# sch_ma_eagle.net
KiCad netlist of a schematic drawn in EAGLE
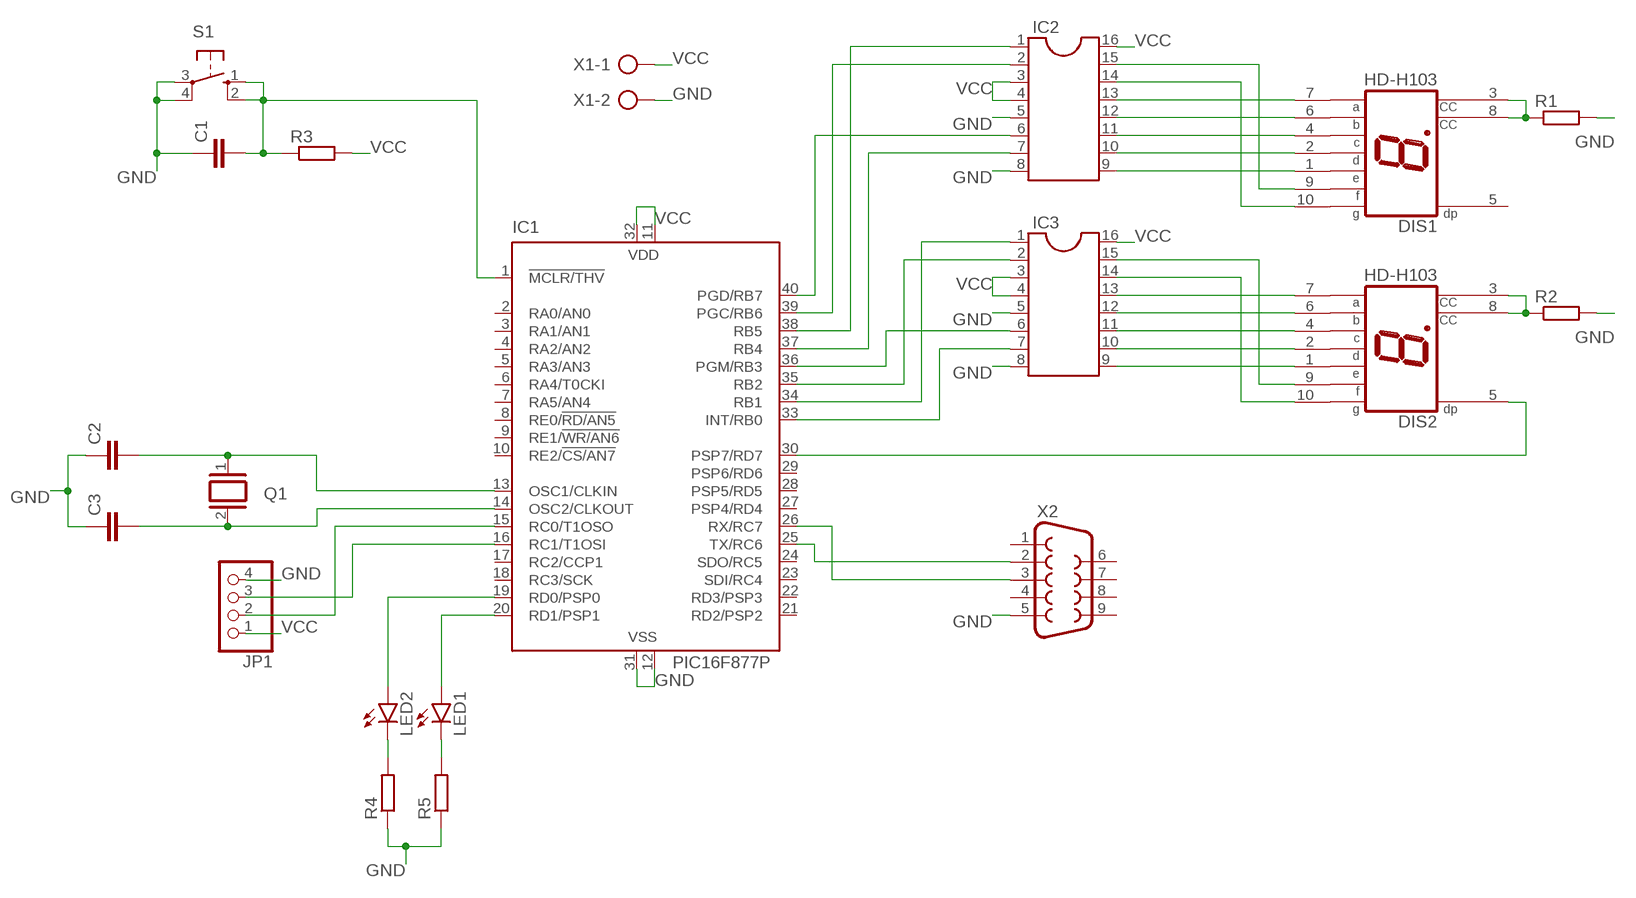
[diagram p0: schematic, sheet 1]

(export (version "E")
  (design (tool "Eeschema 10.0.6"))
  (components
    (comp (ref "C1")
      (value "C-EU025-025X050")
      (footprint "eagle-import:C025-025X050")
      (libsource (lib "eagle-import") (part "C-EU025-025X050"))
    )
    (comp (ref "C2")
      (value "C-EU025-025X050")
      (footprint "eagle-import:C025-025X050")
      (libsource (lib "eagle-import") (part "C-EU025-025X050"))
    )
    (comp (ref "C3")
      (value "C-EU025-025X050")
      (footprint "eagle-import:C025-025X050")
      (libsource (lib "eagle-import") (part "C-EU025-025X050"))
    )
    (comp (ref "DIS1")
      (value "HD-H103")
      (footprint "eagle-import:HDSP-M")
      (libsource (lib "eagle-import") (part "HD-H103"))
    )
    (comp (ref "DIS2")
      (value "HD-H103")
      (footprint "eagle-import:HDSP-M")
      (libsource (lib "eagle-import") (part "HD-H103"))
    )
    (comp (ref "IC1")
      (value "PIC16F877P")
      (footprint "eagle-import:DIL40")
      (fields (field (name "MF") "MICROCHIP") (field (name "MPN") "PIC16F877-04/P"))
      (libsource (lib "eagle-import") (part "PIC16F87P7"))
    )
    (comp (ref "IC2")
      (value "DIL16")
      (footprint "eagle-import:DIL16")
      (libsource (lib "eagle-import") (part "DIL16"))
    )
    (comp (ref "IC3")
      (value "DIL16")
      (footprint "eagle-import:DIL16")
      (libsource (lib "eagle-import") (part "DIL16"))
    )
    (comp (ref "JP1")
      (value "PINHD-1X4")
      (footprint "eagle-import:1X04")
      (libsource (lib "eagle-import") (part "PINHD-1X4"))
    )
    (comp (ref "LED1")
      (value "LED5MM")
      (footprint "eagle-import:LED5MM")
      (libsource (lib "eagle-import") (part "LED5MM"))
    )
    (comp (ref "LED2")
      (value "LED5MM")
      (footprint "eagle-import:LED5MM")
      (libsource (lib "eagle-import") (part "LED5MM"))
    )
    (comp (ref "Q1")
      (value "XTAL/S")
      (footprint "eagle-import:QS")
      (libsource (lib "eagle-import") (part "XTAL/S"))
    )
    (comp (ref "R1")
      (value "R-EU_0207/10")
      (footprint "eagle-import:0207_10")
      (libsource (lib "eagle-import") (part "R-EU_0207/10"))
    )
    (comp (ref "R2")
      (value "R-EU_0207/10")
      (footprint "eagle-import:0207_10")
      (libsource (lib "eagle-import") (part "R-EU_0207/10"))
    )
    (comp (ref "R3")
      (value "R-EU_0207/10")
      (footprint "eagle-import:0207_10")
      (libsource (lib "eagle-import") (part "R-EU_0207/10"))
    )
    (comp (ref "R4")
      (value "R-EU_0207/10")
      (footprint "eagle-import:0207_10")
      (libsource (lib "eagle-import") (part "R-EU_0207/10"))
    )
    (comp (ref "R5")
      (value "R-EU_0207/10")
      (footprint "eagle-import:0207_10")
      (libsource (lib "eagle-import") (part "R-EU_0207/10"))
    )
    (comp (ref "S1")
      (value "10-XX")
      (footprint "eagle-import:B3F-10XX")
      (fields (field (name "MPN") "B3F-1000"))
      (libsource (lib "eagle-import") (part "10-XX"))
    )
    (comp (ref "X1")
      (value "AK300/2")
      (footprint "eagle-import:AK300_2")
      (libsource (lib "eagle-import") (part "AK300/2"))
    )
    (comp (ref "X2")
      (value "F09H")
      (footprint "eagle-import:F09H")
      (libsource (lib "eagle-import") (part "F09H"))
    )
  )
  (nets
    (net (code "1") (name "/GND") (class "Default")
      (node (ref "C1") (pin "1") (pinfunction "1_1") (pintype "passive"))
      (node (ref "C2") (pin "1") (pinfunction "1_1") (pintype "passive"))
      (node (ref "C3") (pin "1") (pinfunction "1_1") (pintype "passive"))
      (node (ref "IC1") (pin "12") (pinfunction "VSS_12") (pintype "power_in"))
      (node (ref "IC1") (pin "31") (pinfunction "VSS_31") (pintype "power_in"))
      (node (ref "IC2") (pin "5") (pinfunction "5_5") (pintype "passive"))
      (node (ref "IC2") (pin "8") (pinfunction "8_8") (pintype "passive"))
      (node (ref "IC3") (pin "5") (pinfunction "5_5") (pintype "passive"))
      (node (ref "IC3") (pin "8") (pinfunction "8_8") (pintype "passive"))
      (node (ref "JP1") (pin "4") (pinfunction "4_4") (pintype "passive"))
      (node (ref "R1") (pin "2") (pinfunction "2_2") (pintype "passive"))
      (node (ref "R2") (pin "2") (pinfunction "2_2") (pintype "passive"))
      (node (ref "R4") (pin "1") (pinfunction "1_1") (pintype "passive"))
      (node (ref "R5") (pin "1") (pinfunction "1_1") (pintype "passive"))
      (node (ref "S1") (pin "3") (pinfunction "P_3") (pintype "passive"))
      (node (ref "S1") (pin "4") (pinfunction "P1_4") (pintype "passive"))
      (node (ref "X1") (pin "2") (pinfunction "KL_2") (pintype "passive"))
      (node (ref "X2") (pin "5") (pinfunction "5_5") (pintype "passive"))
    )
    (net (code "2") (name "/VCC") (class "Default")
      (node (ref "IC1") (pin "11") (pinfunction "VDD_11") (pintype "power_in"))
      (node (ref "IC1") (pin "32") (pinfunction "VDD_32") (pintype "power_in"))
      (node (ref "IC2") (pin "16") (pinfunction "16_16") (pintype "passive"))
      (node (ref "IC2") (pin "3") (pinfunction "3_3") (pintype "passive"))
      (node (ref "IC2") (pin "4") (pinfunction "4_4") (pintype "passive"))
      (node (ref "IC3") (pin "16") (pinfunction "16_16") (pintype "passive"))
      (node (ref "IC3") (pin "3") (pinfunction "3_3") (pintype "passive"))
      (node (ref "IC3") (pin "4") (pinfunction "4_4") (pintype "passive"))
      (node (ref "JP1") (pin "1") (pinfunction "1_1") (pintype "passive"))
      (node (ref "R3") (pin "2") (pinfunction "2_2") (pintype "passive"))
      (node (ref "X1") (pin "1") (pinfunction "KL_1") (pintype "passive"))
    )
    (net (code "3") (name "Net-(DIS1-A)") (class "Default")
      (node (ref "DIS1") (pin "7") (pinfunction "A_7") (pintype "passive"))
      (node (ref "IC2") (pin "13") (pinfunction "13_13") (pintype "passive"))
    )
    (net (code "4") (name "Net-(DIS1-B)") (class "Default")
      (node (ref "DIS1") (pin "6") (pinfunction "B_6") (pintype "passive"))
      (node (ref "IC2") (pin "12") (pinfunction "12_12") (pintype "passive"))
    )
    (net (code "5") (name "Net-(DIS1-C)") (class "Default")
      (node (ref "DIS1") (pin "4") (pinfunction "C_4") (pintype "passive"))
      (node (ref "IC2") (pin "11") (pinfunction "11_11") (pintype "passive"))
    )
    (net (code "6") (name "Net-(DIS1-CC-Pad3)") (class "Default")
      (node (ref "DIS1") (pin "3") (pinfunction "CC_3") (pintype "passive"))
      (node (ref "DIS1") (pin "8") (pinfunction "CC_8") (pintype "passive"))
      (node (ref "R1") (pin "1") (pinfunction "1_1") (pintype "passive"))
    )
    (net (code "7") (name "Net-(DIS1-D)") (class "Default")
      (node (ref "DIS1") (pin "2") (pinfunction "D_2") (pintype "passive"))
      (node (ref "IC2") (pin "10") (pinfunction "10_10") (pintype "passive"))
    )
    (net (code "8") (name "Net-(DIS1-E)") (class "Default")
      (node (ref "DIS1") (pin "1") (pinfunction "E_1") (pintype "passive"))
      (node (ref "IC2") (pin "9") (pinfunction "9_9") (pintype "passive"))
    )
    (net (code "9") (name "Net-(DIS1-F)") (class "Default")
      (node (ref "DIS1") (pin "9") (pinfunction "F_9") (pintype "passive"))
      (node (ref "IC2") (pin "15") (pinfunction "15_15") (pintype "passive"))
    )
    (net (code "10") (name "Net-(DIS1-G)") (class "Default")
      (node (ref "DIS1") (pin "10") (pinfunction "G_10") (pintype "passive"))
      (node (ref "IC2") (pin "14") (pinfunction "14_14") (pintype "passive"))
    )
    (net (code "11") (name "Net-(DIS2-A)") (class "Default")
      (node (ref "DIS2") (pin "7") (pinfunction "A_7") (pintype "passive"))
      (node (ref "IC3") (pin "13") (pinfunction "13_13") (pintype "passive"))
    )
    (net (code "12") (name "Net-(DIS2-B)") (class "Default")
      (node (ref "DIS2") (pin "6") (pinfunction "B_6") (pintype "passive"))
      (node (ref "IC3") (pin "12") (pinfunction "12_12") (pintype "passive"))
    )
    (net (code "13") (name "Net-(DIS2-C)") (class "Default")
      (node (ref "DIS2") (pin "4") (pinfunction "C_4") (pintype "passive"))
      (node (ref "IC3") (pin "11") (pinfunction "11_11") (pintype "passive"))
    )
    (net (code "14") (name "Net-(DIS2-CC-Pad3)") (class "Default")
      (node (ref "DIS2") (pin "3") (pinfunction "CC_3") (pintype "passive"))
      (node (ref "DIS2") (pin "8") (pinfunction "CC_8") (pintype "passive"))
      (node (ref "R2") (pin "1") (pinfunction "1_1") (pintype "passive"))
    )
    (net (code "15") (name "Net-(DIS2-D)") (class "Default")
      (node (ref "DIS2") (pin "2") (pinfunction "D_2") (pintype "passive"))
      (node (ref "IC3") (pin "10") (pinfunction "10_10") (pintype "passive"))
    )
    (net (code "16") (name "Net-(DIS2-DP)") (class "Default")
      (node (ref "DIS2") (pin "5") (pinfunction "DP_5") (pintype "passive"))
      (node (ref "IC1") (pin "30") (pinfunction "PSP7/RD7_30") (pintype "bidirectional"))
    )
    (net (code "17") (name "Net-(DIS2-E)") (class "Default")
      (node (ref "DIS2") (pin "1") (pinfunction "E_1") (pintype "passive"))
      (node (ref "IC3") (pin "9") (pinfunction "9_9") (pintype "passive"))
    )
    (net (code "18") (name "Net-(DIS2-F)") (class "Default")
      (node (ref "DIS2") (pin "9") (pinfunction "F_9") (pintype "passive"))
      (node (ref "IC3") (pin "15") (pinfunction "15_15") (pintype "passive"))
    )
    (net (code "19") (name "Net-(DIS2-G)") (class "Default")
      (node (ref "DIS2") (pin "10") (pinfunction "G_10") (pintype "passive"))
      (node (ref "IC3") (pin "14") (pinfunction "14_14") (pintype "passive"))
    )
    (net (code "20") (name "Net-(IC1-INT{slash}RB0)") (class "Default")
      (node (ref "IC1") (pin "33") (pinfunction "INT/RB0_33") (pintype "bidirectional"))
      (node (ref "IC3") (pin "7") (pinfunction "7_7") (pintype "passive"))
    )
    (net (code "21") (name "Net-(IC1-OSC1{slash}CLKIN)") (class "Default")
      (node (ref "C2") (pin "2") (pinfunction "2_2") (pintype "passive"))
      (node (ref "IC1") (pin "13") (pinfunction "OSC1/CLKIN_13") (pintype "input"))
      (node (ref "Q1") (pin "1") (pinfunction "1_1") (pintype "passive"))
    )
    (net (code "22") (name "Net-(IC1-OSC2{slash}CLKOUT)") (class "Default")
      (node (ref "C3") (pin "2") (pinfunction "2_2") (pintype "passive"))
      (node (ref "IC1") (pin "14") (pinfunction "OSC2/CLKOUT_14") (pintype "output"))
      (node (ref "Q1") (pin "2") (pinfunction "2_2") (pintype "passive"))
    )
    (net (code "23") (name "Net-(IC1-PGC{slash}RB6)") (class "Default")
      (node (ref "IC1") (pin "39") (pinfunction "PGC/RB6_39") (pintype "bidirectional"))
      (node (ref "IC2") (pin "2") (pinfunction "2_2") (pintype "passive"))
    )
    (net (code "24") (name "Net-(IC1-PGD{slash}RB7)") (class "Default")
      (node (ref "IC1") (pin "40") (pinfunction "PGD/RB7_40") (pintype "bidirectional"))
      (node (ref "IC2") (pin "6") (pinfunction "6_6") (pintype "passive"))
    )
    (net (code "25") (name "Net-(IC1-PGM{slash}RB3)") (class "Default")
      (node (ref "IC1") (pin "36") (pinfunction "PGM/RB3_36") (pintype "bidirectional"))
      (node (ref "IC3") (pin "6") (pinfunction "6_6") (pintype "passive"))
    )
    (net (code "26") (name "Net-(IC1-RB1)") (class "Default")
      (node (ref "IC1") (pin "34") (pinfunction "RB1_34") (pintype "bidirectional"))
      (node (ref "IC3") (pin "1") (pinfunction "1_1") (pintype "passive"))
    )
    (net (code "27") (name "Net-(IC1-RB2)") (class "Default")
      (node (ref "IC1") (pin "35") (pinfunction "RB2_35") (pintype "bidirectional"))
      (node (ref "IC3") (pin "2") (pinfunction "2_2") (pintype "passive"))
    )
    (net (code "28") (name "Net-(IC1-RB4)") (class "Default")
      (node (ref "IC1") (pin "37") (pinfunction "RB4_37") (pintype "bidirectional"))
      (node (ref "IC2") (pin "7") (pinfunction "7_7") (pintype "passive"))
    )
    (net (code "29") (name "Net-(IC1-RB5)") (class "Default")
      (node (ref "IC1") (pin "38") (pinfunction "RB5_38") (pintype "bidirectional"))
      (node (ref "IC2") (pin "1") (pinfunction "1_1") (pintype "passive"))
    )
    (net (code "30") (name "Net-(IC1-RC0{slash}T1OSO)") (class "Default")
      (node (ref "IC1") (pin "15") (pinfunction "RC0/T1OSO_15") (pintype "bidirectional"))
      (node (ref "JP1") (pin "2") (pinfunction "2_2") (pintype "passive"))
    )
    (net (code "31") (name "Net-(IC1-RC1{slash}T1OSI)") (class "Default")
      (node (ref "IC1") (pin "16") (pinfunction "RC1/T1OSI_16") (pintype "bidirectional"))
      (node (ref "JP1") (pin "3") (pinfunction "3_3") (pintype "passive"))
    )
    (net (code "32") (name "Net-(IC1-RD0{slash}PSP0)") (class "Default")
      (node (ref "IC1") (pin "19") (pinfunction "RD0/PSP0_19") (pintype "bidirectional"))
      (node (ref "LED2") (pin "A") (pinfunction "A_A") (pintype "passive"))
    )
    (net (code "33") (name "Net-(IC1-RD1{slash}PSP1)") (class "Default")
      (node (ref "IC1") (pin "20") (pinfunction "RD1/PSP1_20") (pintype "bidirectional"))
      (node (ref "LED1") (pin "A") (pinfunction "A_A") (pintype "passive"))
    )
    (net (code "34") (name "Net-(IC1-RX{slash}RC7)") (class "Default")
      (node (ref "IC1") (pin "26") (pinfunction "RX/RC7_26") (pintype "bidirectional"))
      (node (ref "X2") (pin "3") (pinfunction "3_3") (pintype "passive"))
    )
    (net (code "35") (name "Net-(IC1-TX{slash}RC6)") (class "Default")
      (node (ref "IC1") (pin "25") (pinfunction "TX/RC6_25") (pintype "bidirectional"))
      (node (ref "X2") (pin "2") (pinfunction "2_2") (pintype "passive"))
    )
    (net (code "36") (name "Net-(IC1-~{MCLR{slash}THV})") (class "Default")
      (node (ref "C1") (pin "2") (pinfunction "2_2") (pintype "passive"))
      (node (ref "IC1") (pin "1") (pinfunction "~{MCLR/THV}_1") (pintype "input"))
      (node (ref "R3") (pin "1") (pinfunction "1_1") (pintype "passive"))
      (node (ref "S1") (pin "1") (pinfunction "S_1") (pintype "passive"))
      (node (ref "S1") (pin "2") (pinfunction "S1_2") (pintype "passive"))
    )
    (net (code "37") (name "Net-(LED1-C)") (class "Default")
      (node (ref "LED1") (pin "K") (pinfunction "C_K") (pintype "passive"))
      (node (ref "R5") (pin "2") (pinfunction "2_2") (pintype "passive"))
    )
    (net (code "38") (name "Net-(LED2-C)") (class "Default")
      (node (ref "LED2") (pin "K") (pinfunction "C_K") (pintype "passive"))
      (node (ref "R4") (pin "2") (pinfunction "2_2") (pintype "passive"))
    )
    (net (code "39") (name "unconnected-(DIS1-DP-Pad5)") (class "Default")
      (node (ref "DIS1") (pin "5") (pinfunction "DP_5") (pintype "passive"))
    )
    (net (code "40") (name "unconnected-(IC1-PSP4{slash}RD4-Pad27)") (class "Default")
      (node (ref "IC1") (pin "27") (pinfunction "PSP4/RD4_27") (pintype "bidirectional"))
    )
    (net (code "41") (name "unconnected-(IC1-PSP5{slash}RD5-Pad28)") (class "Default")
      (node (ref "IC1") (pin "28") (pinfunction "PSP5/RD5_28") (pintype "bidirectional"))
    )
    (net (code "42") (name "unconnected-(IC1-PSP6{slash}RD6-Pad29)") (class "Default")
      (node (ref "IC1") (pin "29") (pinfunction "PSP6/RD6_29") (pintype "bidirectional"))
    )
    (net (code "43") (name "unconnected-(IC1-RA0{slash}AN0-Pad2)") (class "Default")
      (node (ref "IC1") (pin "2") (pinfunction "RA0/AN0_2") (pintype "bidirectional"))
    )
    (net (code "44") (name "unconnected-(IC1-RA1{slash}AN1-Pad3)") (class "Default")
      (node (ref "IC1") (pin "3") (pinfunction "RA1/AN1_3") (pintype "bidirectional"))
    )
    (net (code "45") (name "unconnected-(IC1-RA2{slash}AN2-Pad4)") (class "Default")
      (node (ref "IC1") (pin "4") (pinfunction "RA2/AN2_4") (pintype "bidirectional"))
    )
    (net (code "46") (name "unconnected-(IC1-RA3{slash}AN3-Pad5)") (class "Default")
      (node (ref "IC1") (pin "5") (pinfunction "RA3/AN3_5") (pintype "bidirectional"))
    )
    (net (code "47") (name "unconnected-(IC1-RA4{slash}T0CKI-Pad6)") (class "Default")
      (node (ref "IC1") (pin "6") (pinfunction "RA4/T0CKI_6") (pintype "bidirectional"))
    )
    (net (code "48") (name "unconnected-(IC1-RA5{slash}AN4-Pad7)") (class "Default")
      (node (ref "IC1") (pin "7") (pinfunction "RA5/AN4_7") (pintype "bidirectional"))
    )
    (net (code "49") (name "unconnected-(IC1-RC2{slash}CCP1-Pad17)") (class "Default")
      (node (ref "IC1") (pin "17") (pinfunction "RC2/CCP1_17") (pintype "bidirectional"))
    )
    (net (code "50") (name "unconnected-(IC1-RC3{slash}SCK-Pad18)") (class "Default")
      (node (ref "IC1") (pin "18") (pinfunction "RC3/SCK_18") (pintype "bidirectional"))
    )
    (net (code "51") (name "unconnected-(IC1-RD2{slash}PSP2-Pad21)") (class "Default")
      (node (ref "IC1") (pin "21") (pinfunction "RD2/PSP2_21") (pintype "bidirectional"))
    )
    (net (code "52") (name "unconnected-(IC1-RD3{slash}PSP3-Pad22)") (class "Default")
      (node (ref "IC1") (pin "22") (pinfunction "RD3/PSP3_22") (pintype "bidirectional"))
    )
    (net (code "53") (name "unconnected-(IC1-RE0{slash}~{RD{slash}AN5}-Pad8)") (class "Default")
      (node (ref "IC1") (pin "8") (pinfunction "RE0/~{RD/AN5}_8") (pintype "bidirectional"))
    )
    (net (code "54") (name "unconnected-(IC1-RE1{slash}~{WR{slash}AN6}-Pad9)") (class "Default")
      (node (ref "IC1") (pin "9") (pinfunction "RE1/~{WR/AN6}_9") (pintype "bidirectional"))
    )
    (net (code "55") (name "unconnected-(IC1-RE2{slash}~{CS{slash}AN7}-Pad10)") (class "Default")
      (node (ref "IC1") (pin "10") (pinfunction "RE2/~{CS/AN7}_10") (pintype "bidirectional"))
    )
    (net (code "56") (name "unconnected-(IC1-SDI{slash}RC4-Pad23)") (class "Default")
      (node (ref "IC1") (pin "23") (pinfunction "SDI/RC4_23") (pintype "bidirectional"))
    )
    (net (code "57") (name "unconnected-(IC1-SDO{slash}RC5-Pad24)") (class "Default")
      (node (ref "IC1") (pin "24") (pinfunction "SDO/RC5_24") (pintype "bidirectional"))
    )
    (net (code "58") (name "unconnected-(X2-Pad1)") (class "Default")
      (node (ref "X2") (pin "1") (pinfunction "1_1") (pintype "passive"))
    )
    (net (code "59") (name "unconnected-(X2-Pad4)") (class "Default")
      (node (ref "X2") (pin "4") (pinfunction "4_4") (pintype "passive"))
    )
    (net (code "60") (name "unconnected-(X2-Pad6)") (class "Default")
      (node (ref "X2") (pin "6") (pinfunction "6_6") (pintype "passive"))
    )
    (net (code "61") (name "unconnected-(X2-Pad7)") (class "Default")
      (node (ref "X2") (pin "7") (pinfunction "7_7") (pintype "passive"))
    )
    (net (code "62") (name "unconnected-(X2-Pad8)") (class "Default")
      (node (ref "X2") (pin "8") (pinfunction "8_8") (pintype "passive"))
    )
    (net (code "63") (name "unconnected-(X2-Pad9)") (class "Default")
      (node (ref "X2") (pin "9") (pinfunction "9_9") (pintype "passive"))
    )
  )
)
